# stm32wl_Power.net
KiCad netlist of a schematic drawn in Altium Designer
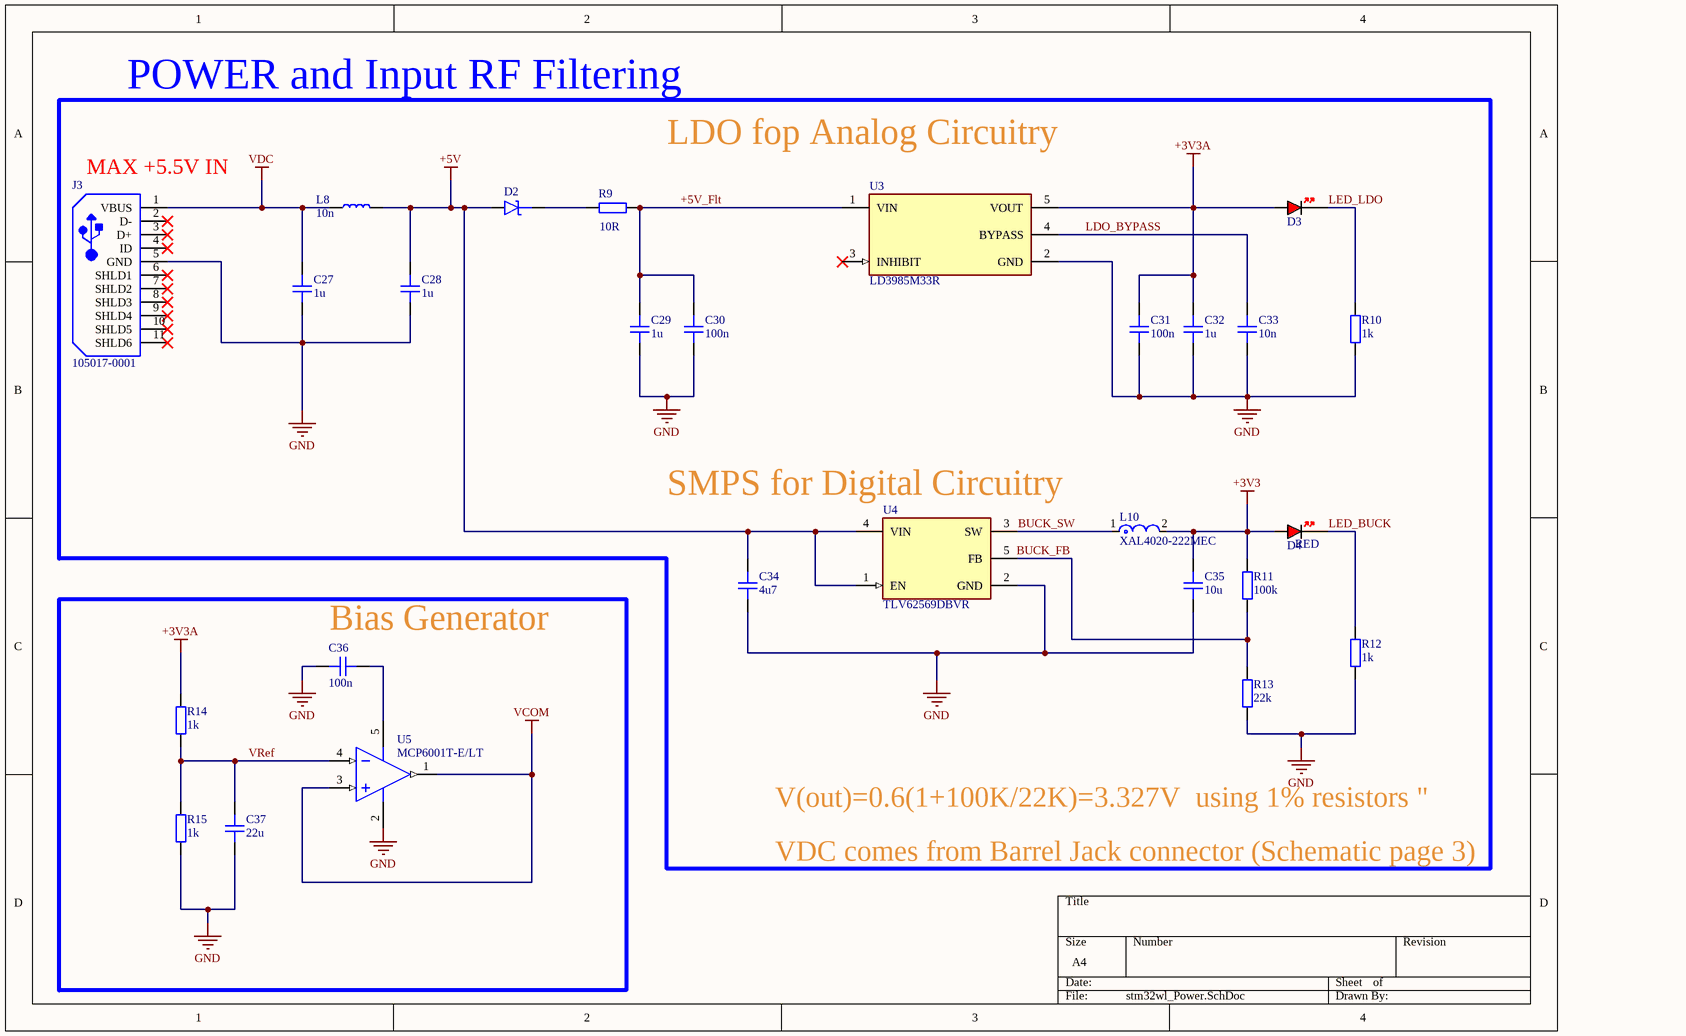
[diagram p0: stm32wl_Power.SchDoc]

(export (version "E")
  (design (tool "Eeschema 10.0.6"))
  (components
    (comp (ref "C27")
      (value "1u")
      (footprint "CAP_0603")
      (description "Capacitor SMD 0603 16V")
      (libsource (lib "Schematic-Lib-PhilsLab") (part "CAP_0603_16V"))
    )
    (comp (ref "C28")
      (value "1u")
      (footprint "CAP_0603")
      (description "Capacitor SMD 0603 16V")
      (libsource (lib "Schematic-Lib-PhilsLab") (part "CAP_0603_16V"))
    )
    (comp (ref "C29")
      (value "1u")
      (footprint "CAP_0603")
      (description "Capacitor SMD 0603 16V")
      (libsource (lib "Schematic-Lib-PhilsLab") (part "CAP_0603_16V"))
    )
    (comp (ref "C30")
      (value "100n")
      (footprint "CAP_0603")
      (description "Capacitor SMD 0603 16V")
      (libsource (lib "Schematic-Lib-PhilsLab") (part "CAP_0603_16V"))
    )
    (comp (ref "C31")
      (value "100n")
      (footprint "CAP_0603")
      (description "Capacitor SMD 0603 16V")
      (libsource (lib "Schematic-Lib-PhilsLab") (part "CAP_0603_16V"))
    )
    (comp (ref "C32")
      (value "1u")
      (footprint "CAP_0603")
      (description "Capacitor SMD 0603 16V")
      (libsource (lib "Schematic-Lib-PhilsLab") (part "CAP_0603_16V"))
    )
    (comp (ref "C33")
      (value "10n")
      (footprint "CAP_0603")
      (description "Capacitor SMD 0603 16V")
      (libsource (lib "Schematic-Lib-PhilsLab") (part "CAP_0603_16V"))
    )
    (comp (ref "C34")
      (value "4u7")
      (footprint "CAP_0603")
      (description "Capacitor SMD 0603 16V")
      (libsource (lib "Schematic-Lib-PhilsLab") (part "CAP_0603_16V"))
    )
    (comp (ref "C35")
      (value "10u")
      (footprint "CAP_0603")
      (description "Capacitor SMD 0603 16V")
      (libsource (lib "Schematic-Lib-PhilsLab") (part "CAP_0603_16V"))
    )
    (comp (ref "C36")
      (value "100n")
      (footprint "CAP_0402")
      (description "Capacitor SMD 0402 16V")
      (libsource (lib "Schematic-Lib-PhilsLab") (part "CAP_0402_16V"))
    )
    (comp (ref "C37")
      (value "22u")
      (footprint "CAP_0603")
      (description "Capacitor SMD 0603 16V")
      (libsource (lib "Schematic-Lib-PhilsLab") (part "CAP_0603_16V"))
    )
    (comp (ref "D2")
      (value "D_SCHOTTKY_SOD_323")
      (footprint "SOD-323")
      (description "Diode Schottky SMD SOD-323")
      (libsource (lib "Schematic-Lib-PhilsLab") (part "D_SCHOTTKY_SOD_323"))
    )
    (comp (ref "D3")
      (value "RED")
      (footprint "LED_0402_RED")
      (description "LED 0402 RED SMD")
      (libsource (lib "Schematic-Lib-PhilsLab") (part "LED_0402_RED"))
    )
    (comp (ref "D4")
      (value "RED")
      (footprint "LED_0402_RED")
      (description "LED 0402 RED SMD")
      (libsource (lib "Schematic-Lib-PhilsLab") (part "LED_0402_RED"))
    )
    (comp (ref "J3")
      (value "105017-0001")
      (footprint "USB-MICRO-B_V")
      (fields (field (name "MANUFACTURER") "Molex"))
      (libsource (lib "Altium Content Vault") (part "USB-5-6SHLD"))
    )
    (comp (ref "L8")
      (value "10n")
      (footprint "IND_0603")
      (description "Inductor SMD 0603")
      (libsource (lib "Schematic-Lib-PhilsLab") (part "IND_0603"))
    )
    (comp (ref "L10")
      (value "XAL4020-222MEC")
      (footprint "FP-XAL4020-MFG")
      (description "Fixed Inductors 2.2uH Shld 20% 5.5A 38.7mOhms AECQ2")
      (fields (field (name "TOLERANCE") "20%"))
      (libsource (lib "XAL4020-222ME") (part "CMP-11268-000134-1"))
    )
    (comp (ref "R9")
      (value "10R")
      (footprint "RES_0603")
      (description "Resistor SMD 0603")
      (libsource (lib "Schematic-Lib-PhilsLab") (part "RES_0603"))
    )
    (comp (ref "R10")
      (value "1k")
      (footprint "RES_0402")
      (description "Resistor SMD 0402")
      (libsource (lib "Schematic-Lib-PhilsLab") (part "RES_0402"))
    )
    (comp (ref "R11")
      (value "100k")
      (footprint "RES_0402")
      (description "Resistor SMD 0402")
      (libsource (lib "Schematic-Lib-PhilsLab") (part "RES_0402"))
    )
    (comp (ref "R12")
      (value "1k")
      (footprint "RES_0402")
      (description "Resistor SMD 0402")
      (libsource (lib "Schematic-Lib-PhilsLab") (part "RES_0402"))
    )
    (comp (ref "R13")
      (value "22k")
      (footprint "RES_0402")
      (description "Resistor SMD 0402")
      (libsource (lib "Schematic-Lib-PhilsLab") (part "RES_0402"))
    )
    (comp (ref "R14")
      (value "1k")
      (footprint "RES_0402")
      (description "Resistor SMD 0402")
      (libsource (lib "Schematic-Lib-PhilsLab") (part "RES_0402"))
    )
    (comp (ref "R15")
      (value "1k")
      (footprint "RES_0402")
      (description "Resistor SMD 0402")
      (libsource (lib "Schematic-Lib-PhilsLab") (part "RES_0402"))
    )
    (comp (ref "U3")
      (value "LD3985M33R")
      (footprint "FP-SOT23-5L-7049676-IPC_C")
      (libsource (lib "LD3985M33R") (part "CMP-0244-00328-3"))
    )
    (comp (ref "U4")
      (value "TLV62569DBVR")
      (footprint "FP-DBV0005A-MFG")
      (description "IC REG BUCK ADJ 2A SOT23-5")
      (libsource (lib "Altium Content Vault") (part "f8671745ee5fb9a493b385c735b730b"))
    )
    (comp (ref "U5")
      (value "MCP6001T-E/LT")
      (footprint "SC70-LT5_L")
      (description "None")
      (libsource (lib "Altium Content Vault") (part "AMP-OPA-MCP6001-SOT5"))
    )
  )
  (nets
    (net (code "1") (name "+3V3") (class "Default")
      (node (ref "C35") (pin "2") (pinfunction "2_2") (pintype "passive"))
      (node (ref "D4") (pin "A") (pinfunction "A_A") (pintype "passive"))
      (node (ref "L10") (pin "2") (pinfunction "2_2") (pintype "passive"))
      (node (ref "R11") (pin "2") (pinfunction "2_2") (pintype "passive"))
    )
    (net (code "2") (name "+3V3A") (class "Default")
      (node (ref "C31") (pin "2") (pinfunction "2_2") (pintype "passive"))
      (node (ref "C32") (pin "2") (pinfunction "2_2") (pintype "passive"))
      (node (ref "D3") (pin "A") (pinfunction "A_A") (pintype "passive"))
      (node (ref "R14") (pin "2") (pinfunction "2_2") (pintype "passive"))
      (node (ref "U3") (pin "5") (pinfunction "VOUT_5") (pintype "passive"))
    )
    (net (code "3") (name "+5V") (class "Default")
      (node (ref "C28") (pin "2") (pinfunction "2_2") (pintype "passive"))
      (node (ref "C34") (pin "2") (pinfunction "2_2") (pintype "passive"))
      (node (ref "D2") (pin "A") (pinfunction "A_A") (pintype "passive"))
      (node (ref "L8") (pin "2") (pinfunction "2_2") (pintype "passive"))
      (node (ref "U4") (pin "1") (pinfunction "EN_1") (pintype "input"))
      (node (ref "U4") (pin "4") (pinfunction "VIN_4") (pintype "power_in"))
    )
    (net (code "4") (name "/+5V_Flt") (class "Default")
      (node (ref "C29") (pin "2") (pinfunction "2_2") (pintype "passive"))
      (node (ref "C30") (pin "2") (pinfunction "2_2") (pintype "passive"))
      (node (ref "R9") (pin "2") (pinfunction "2_2") (pintype "passive"))
      (node (ref "U3") (pin "1") (pinfunction "VIN_1") (pintype "power_in"))
    )
    (net (code "5") (name "/BUCK_FB") (class "Default")
      (node (ref "R11") (pin "1") (pinfunction "1_1") (pintype "passive"))
      (node (ref "R13") (pin "2") (pinfunction "2_2") (pintype "passive"))
      (node (ref "U4") (pin "5") (pinfunction "FB_5") (pintype "passive"))
    )
    (net (code "6") (name "/BUCK_SW") (class "Default")
      (node (ref "L10") (pin "1") (pinfunction "1_1") (pintype "passive"))
      (node (ref "U4") (pin "3") (pinfunction "SW_3") (pintype "power_in"))
    )
    (net (code "7") (name "/LDO_BYPASS") (class "Default")
      (node (ref "C33") (pin "2") (pinfunction "2_2") (pintype "passive"))
      (node (ref "U3") (pin "4") (pinfunction "BYPASS_4") (pintype "passive"))
    )
    (net (code "8") (name "/LED_BUCK") (class "Default")
      (node (ref "D4") (pin "K") (pinfunction "K_K") (pintype "passive"))
      (node (ref "R12") (pin "2") (pinfunction "2_2") (pintype "passive"))
    )
    (net (code "9") (name "/LED_LDO") (class "Default")
      (node (ref "D3") (pin "K") (pinfunction "K_K") (pintype "passive"))
      (node (ref "R10") (pin "2") (pinfunction "2_2") (pintype "passive"))
    )
    (net (code "10") (name "/VRef") (class "Default")
      (node (ref "C37") (pin "2") (pinfunction "2_2") (pintype "passive"))
      (node (ref "R14") (pin "1") (pinfunction "1_1") (pintype "passive"))
      (node (ref "R15") (pin "2") (pinfunction "2_2") (pintype "passive"))
      (node (ref "U5") (pin "4") (pinfunction "VIN-_4") (pintype "input"))
    )
    (net (code "11") (name "GND") (class "Default")
      (node (ref "C27") (pin "1") (pinfunction "1_1") (pintype "passive"))
      (node (ref "C28") (pin "1") (pinfunction "1_1") (pintype "passive"))
      (node (ref "C29") (pin "1") (pinfunction "1_1") (pintype "passive"))
      (node (ref "C30") (pin "1") (pinfunction "1_1") (pintype "passive"))
      (node (ref "C31") (pin "1") (pinfunction "1_1") (pintype "passive"))
      (node (ref "C32") (pin "1") (pinfunction "1_1") (pintype "passive"))
      (node (ref "C33") (pin "1") (pinfunction "1_1") (pintype "passive"))
      (node (ref "C34") (pin "1") (pinfunction "1_1") (pintype "passive"))
      (node (ref "C35") (pin "1") (pinfunction "1_1") (pintype "passive"))
      (node (ref "C36") (pin "2") (pinfunction "2_2") (pintype "passive"))
      (node (ref "C37") (pin "1") (pinfunction "1_1") (pintype "passive"))
      (node (ref "J3") (pin "5") (pinfunction "GND_5") (pintype "passive"))
      (node (ref "R10") (pin "1") (pinfunction "1_1") (pintype "passive"))
      (node (ref "R12") (pin "1") (pinfunction "1_1") (pintype "passive"))
      (node (ref "R13") (pin "1") (pinfunction "1_1") (pintype "passive"))
      (node (ref "R15") (pin "1") (pinfunction "1_1") (pintype "passive"))
      (node (ref "U3") (pin "2") (pinfunction "GND_2") (pintype "power_in"))
      (node (ref "U4") (pin "2") (pinfunction "GND_2") (pintype "power_in"))
      (node (ref "U5") (pin "2") (pinfunction "VSS_2") (pintype "power_in"))
    )
    (net (code "12") (name "Net-(D2-PadK)") (class "Default")
      (node (ref "D2") (pin "K") (pinfunction "K_K") (pintype "passive"))
      (node (ref "R9") (pin "1") (pinfunction "1_1") (pintype "passive"))
    )
    (net (code "13") (name "Net-(U5-VDD)") (class "Default")
      (node (ref "C36") (pin "1") (pinfunction "1_1") (pintype "passive"))
      (node (ref "U5") (pin "5") (pinfunction "VDD_5") (pintype "power_in"))
    )
    (net (code "14") (name "VCOM") (class "Default")
      (node (ref "U5") (pin "1") (pinfunction "VOUT_1") (pintype "output"))
      (node (ref "U5") (pin "3") (pinfunction "VIN+_3") (pintype "input"))
    )
    (net (code "15") (name "VDC") (class "Default")
      (node (ref "C27") (pin "2") (pinfunction "2_2") (pintype "passive"))
      (node (ref "J3") (pin "1") (pinfunction "VBUS_1") (pintype "passive"))
      (node (ref "L8") (pin "1") (pinfunction "1_1") (pintype "passive"))
    )
    (net (code "16") (name "unconnected-(J3-D+-Pad3)") (class "Default")
      (node (ref "J3") (pin "3") (pinfunction "D+_3") (pintype "passive+no_connect"))
    )
    (net (code "17") (name "unconnected-(J3-D--Pad2)") (class "Default")
      (node (ref "J3") (pin "2") (pinfunction "D-_2") (pintype "passive+no_connect"))
    )
    (net (code "18") (name "unconnected-(J3-ID-Pad4)") (class "Default")
      (node (ref "J3") (pin "4") (pinfunction "ID_4") (pintype "passive+no_connect"))
    )
    (net (code "19") (name "unconnected-(J3-SHLD1-Pad6)") (class "Default")
      (node (ref "J3") (pin "6") (pinfunction "SHLD1_6") (pintype "passive+no_connect"))
    )
    (net (code "20") (name "unconnected-(J3-SHLD2-Pad7)") (class "Default")
      (node (ref "J3") (pin "7") (pinfunction "SHLD2_7") (pintype "passive+no_connect"))
    )
    (net (code "21") (name "unconnected-(J3-SHLD3-Pad8)") (class "Default")
      (node (ref "J3") (pin "8") (pinfunction "SHLD3_8") (pintype "passive+no_connect"))
    )
    (net (code "22") (name "unconnected-(J3-SHLD4-Pad9)") (class "Default")
      (node (ref "J3") (pin "9") (pinfunction "SHLD4_9") (pintype "passive+no_connect"))
    )
    (net (code "23") (name "unconnected-(J3-SHLD5-Pad10)") (class "Default")
      (node (ref "J3") (pin "10") (pinfunction "SHLD5_10") (pintype "passive+no_connect"))
    )
    (net (code "24") (name "unconnected-(J3-SHLD6-Pad11)") (class "Default")
      (node (ref "J3") (pin "11") (pinfunction "SHLD6_11") (pintype "passive+no_connect"))
    )
    (net (code "25") (name "unconnected-(U3-INHIBIT-Pad3)") (class "Default")
      (node (ref "U3") (pin "3") (pinfunction "INHIBIT_3") (pintype "input+no_connect"))
    )
  )
)
